# RS485_RGB_Power.net
KiCad netlist of a schematic drawn in Altium Designer
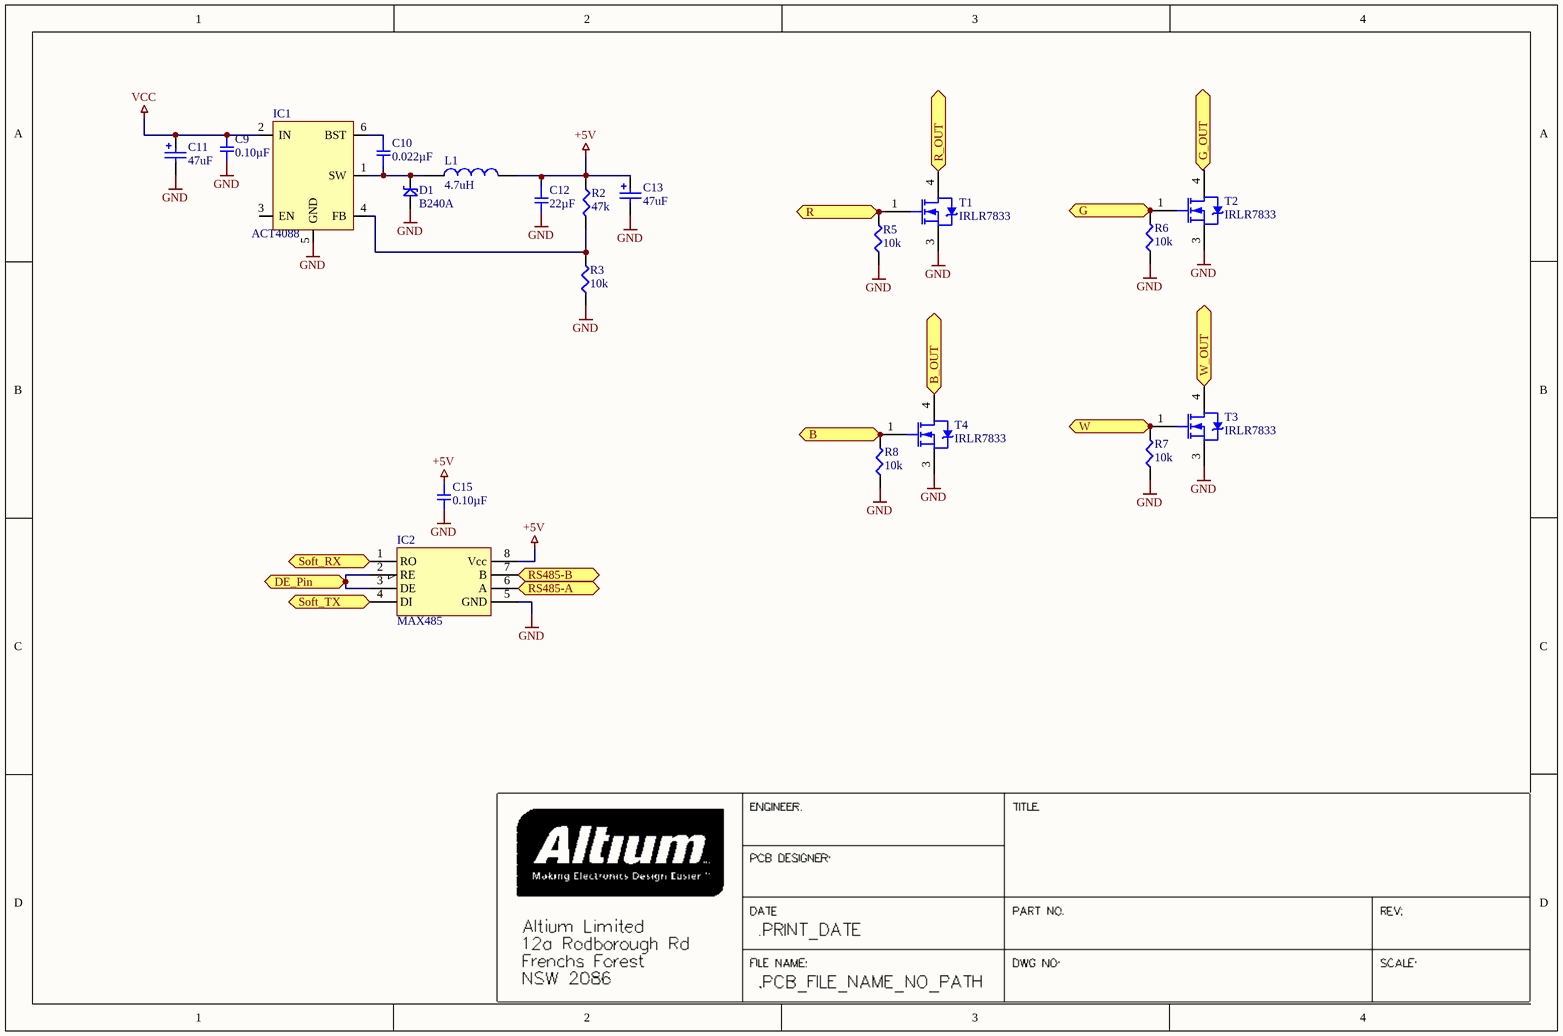
[diagram p0: RS485_RGB_Power.SchDoc]

(export (version "E")
  (design (tool "Eeschema 10.0.6"))
  (components
    (comp (ref "C9")
      (value "0.10µF")
      (footprint "SMD-0603C")
      (description "CAP CER 0.1UF 100V X7R 0603")
      (fields
        (field (name "DIGI-KEY PART NUMBER") "490-13420-1-ND")
        (field (name "PART NUMBER") "GCJ188R72A104KA01D")
      )
      (libsource (lib "capacitor_murata_0603") (part "GCJ188R72A104KA01D"))
    )
    (comp (ref "C10")
      (value "0.022µF")
      (footprint "SMD-0603C")
      (description "CAP CER 0.022UF 50V X7R 0603")
      (fields
        (field (name "DIGI-KEY PART NUMBER") "490-5851-1-ND")
        (field (name "PART NUMBER") "GCJ188R71H223KA01D")
      )
      (libsource (lib "capacitor_murata_0603") (part "GCJ188R71H223KA01D"))
    )
    (comp (ref "C11")
      (value "47uF")
      (footprint "WCAP-ASLI_6.3x5.5")
      (description "WCAP-ASLI Aluminum Electrolytic Capacitors, size Ф6.3x5.5mm, 35V DC, 47uF")
      (fields (field (name "PART NUMBER") "865080543009") (field (name "PUBLISHER") "Wurth Elektronik"))
      (libsource (lib "ALTIUM-WCAP-ASLI-rev17a") (part "865080543009"))
    )
    (comp (ref "C12")
      (value "22µF")
      (footprint "SMD-0603C")
      (description "CAP CER 22UF 4V X5R 0603")
      (fields
        (field (name "DIGI-KEY PART NUMBER") "490-13240-1-ND")
        (field (name "PART NUMBER") "GRM186R60G226ME15D")
      )
      (libsource (lib "capacitor_murata_0603") (part "GRM186R60G226ME15D"))
    )
    (comp (ref "C13")
      (value "47uF")
      (footprint "WCAP-ASLI_6.3x5.5")
      (description "WCAP-ASLI Aluminum Electrolytic Capacitors, size Ф6.3x5.5mm, 35V DC, 47uF")
      (fields (field (name "PART NUMBER") "865080543009") (field (name "PUBLISHER") "Wurth Elektronik"))
      (libsource (lib "ALTIUM-WCAP-ASLI-rev17a") (part "865080543009"))
    )
    (comp (ref "C15")
      (value "0.10µF")
      (footprint "SMD-0603C")
      (description "CAP CER 0.1UF 100V X7R 0603")
      (fields
        (field (name "DIGI-KEY PART NUMBER") "490-13420-1-ND")
        (field (name "PART NUMBER") "GCJ188R72A104KA01D")
      )
      (libsource (lib "capacitor_murata_0603") (part "GCJ188R72A104KA01D"))
    )
    (comp (ref "D1")
      (value "B240A")
      (footprint "B240A")
      (description "Shottkydiode")
      (libsource (lib "MyLibs") (part "B240A"))
    )
    (comp (ref "IC1") (value "ACT4088") (footprint "SOT23-6") (libsource (lib "MyLibs") (part "ACT4088")))
    (comp (ref "IC2") (value "MAX485") (footprint "D008_L") (libsource (lib "MyLibs") (part "MAX485")))
    (comp (ref "L1")
      (value "4.7uH")
      (footprint "WE-TPC_2813")
      (description "WE-TPC SMD Shielded Tiny Power Inductor, size 2813, 1A, 170mΩ, 4.7uH")
      (fields (field (name "PART NUMBER") "744029004") (field (name "PUBLISHER") "Wurth Elektronik"))
      (libsource (lib "ALTIUM-WE-TPC-rev17a") (part "744029004"))
    )
    (comp (ref "R2")
      (value "47k")
      (footprint "SMD-0603-RES")
      (description "RES SMD 47K OHM 1% 1/10W 0603")
      (fields
        (field (name "PART NUMBER") "ERJ-3EKF4702V")
        (field (name "DIGI-KEY PART NUMBER") "P47.0KHCT-ND")
      )
      (libsource (lib "Panasonic_ERJ_0603") (part "ERJ-3EKF4702V"))
    )
    (comp (ref "R3")
      (value "10k")
      (footprint "SMD-0603-RES")
      (description "RES SMD 10K OHM 1% 1/10W 0603")
      (fields
        (field (name "PART NUMBER") "ERJ-3EKF1002V")
        (field (name "DIGI-KEY PART NUMBER") "P10.0KHCT-ND")
      )
      (libsource (lib "Panasonic_ERJ_0603") (part "ERJ-3EKF1002V"))
    )
    (comp (ref "R5")
      (value "10k")
      (footprint "SMD-0603-RES")
      (description "RES SMD 10K OHM 1% 1/10W 0603")
      (fields
        (field (name "PART NUMBER") "ERJ-3EKF1002V")
        (field (name "DIGI-KEY PART NUMBER") "P10.0KHCT-ND")
      )
      (libsource (lib "Panasonic_ERJ_0603") (part "ERJ-3EKF1002V"))
    )
    (comp (ref "R6")
      (value "10k")
      (footprint "SMD-0603-RES")
      (description "RES SMD 10K OHM 1% 1/10W 0603")
      (fields
        (field (name "PART NUMBER") "ERJ-3EKF1002V")
        (field (name "DIGI-KEY PART NUMBER") "P10.0KHCT-ND")
      )
      (libsource (lib "Panasonic_ERJ_0603") (part "ERJ-3EKF1002V"))
    )
    (comp (ref "R7")
      (value "10k")
      (footprint "SMD-0603-RES")
      (description "RES SMD 10K OHM 1% 1/10W 0603")
      (fields
        (field (name "PART NUMBER") "ERJ-3EKF1002V")
        (field (name "DIGI-KEY PART NUMBER") "P10.0KHCT-ND")
      )
      (libsource (lib "Panasonic_ERJ_0603") (part "ERJ-3EKF1002V"))
    )
    (comp (ref "R8")
      (value "10k")
      (footprint "SMD-0603-RES")
      (description "RES SMD 10K OHM 1% 1/10W 0603")
      (fields
        (field (name "PART NUMBER") "ERJ-3EKF1002V")
        (field (name "DIGI-KEY PART NUMBER") "P10.0KHCT-ND")
      )
      (libsource (lib "Panasonic_ERJ_0603") (part "ERJ-3EKF1002V"))
    )
    (comp (ref "T1")
      (value "IRLR7833")
      (footprint "ONSC-DPAK-3-369C-01_V")
      (description "N-Channel MOSFET")
      (libsource (lib "MyLibs") (part "IRLR7833"))
    )
    (comp (ref "T2")
      (value "IRLR7833")
      (footprint "ONSC-DPAK-3-369C-01_V")
      (description "N-Channel MOSFET")
      (libsource (lib "MyLibs") (part "IRLR7833"))
    )
    (comp (ref "T3")
      (value "IRLR7833")
      (footprint "ONSC-DPAK-3-369C-01_V")
      (description "N-Channel MOSFET")
      (libsource (lib "MyLibs") (part "IRLR7833"))
    )
    (comp (ref "T4")
      (value "IRLR7833")
      (footprint "ONSC-DPAK-3-369C-01_V")
      (description "N-Channel MOSFET")
      (libsource (lib "MyLibs") (part "IRLR7833"))
    )
  )
  (nets
    (net (code "1") (name "+5V") (class "Default")
      (node (ref "C12") (pin "1") (pinfunction "1_1") (pintype "passive"))
      (node (ref "C13") (pin "1") (pinfunction "P_1") (pintype "passive"))
      (node (ref "C15") (pin "1") (pinfunction "1_1") (pintype "passive"))
      (node (ref "IC2") (pin "8") (pinfunction "Vcc_8") (pintype "passive"))
      (node (ref "L1") (pin "2") (pinfunction "2_2") (pintype "passive"))
      (node (ref "R2") (pin "1") (pinfunction "1_1") (pintype "passive"))
    )
    (net (code "2") (name "/B") (class "Default")
      (node (ref "R8") (pin "2") (pinfunction "2_2") (pintype "passive"))
      (node (ref "T4") (pin "1") (pinfunction "G_1") (pintype "passive"))
    )
    (net (code "3") (name "/B_OUT") (class "Default")
      (node (ref "T4") (pin "4") (pinfunction "D_4") (pintype "passive"))
    )
    (net (code "4") (name "/DE_Pin") (class "Default")
      (node (ref "IC2") (pin "2") (pinfunction "RE_2") (pintype "passive"))
      (node (ref "IC2") (pin "3") (pinfunction "DE_3") (pintype "passive"))
    )
    (net (code "5") (name "/G") (class "Default")
      (node (ref "R6") (pin "2") (pinfunction "2_2") (pintype "passive"))
      (node (ref "T2") (pin "1") (pinfunction "G_1") (pintype "passive"))
    )
    (net (code "6") (name "/G_OUT") (class "Default")
      (node (ref "T2") (pin "4") (pinfunction "D_4") (pintype "passive"))
    )
    (net (code "7") (name "/R") (class "Default")
      (node (ref "R5") (pin "2") (pinfunction "2_2") (pintype "passive"))
      (node (ref "T1") (pin "1") (pinfunction "G_1") (pintype "passive"))
    )
    (net (code "8") (name "/RS485-A") (class "Default")
      (node (ref "IC2") (pin "6") (pinfunction "A_6") (pintype "passive"))
    )
    (net (code "9") (name "/RS485-B") (class "Default")
      (node (ref "IC2") (pin "7") (pinfunction "B_7") (pintype "passive"))
    )
    (net (code "10") (name "/R_OUT") (class "Default")
      (node (ref "T1") (pin "4") (pinfunction "D_4") (pintype "passive"))
    )
    (net (code "11") (name "/Soft_RX") (class "Default")
      (node (ref "IC2") (pin "1") (pinfunction "RO_1") (pintype "passive"))
    )
    (net (code "12") (name "/Soft_TX") (class "Default")
      (node (ref "IC2") (pin "4") (pinfunction "DI_4") (pintype "passive"))
    )
    (net (code "13") (name "/W") (class "Default")
      (node (ref "R7") (pin "2") (pinfunction "2_2") (pintype "passive"))
      (node (ref "T3") (pin "1") (pinfunction "G_1") (pintype "passive"))
    )
    (net (code "14") (name "/W_OUT") (class "Default")
      (node (ref "T3") (pin "4") (pinfunction "D_4") (pintype "passive"))
    )
    (net (code "15") (name "GND") (class "Default")
      (node (ref "C11") (pin "2") (pinfunction "N_2") (pintype "passive"))
      (node (ref "C12") (pin "2") (pinfunction "2_2") (pintype "passive"))
      (node (ref "C13") (pin "2") (pinfunction "N_2") (pintype "passive"))
      (node (ref "C15") (pin "2") (pinfunction "2_2") (pintype "passive"))
      (node (ref "C9") (pin "2") (pinfunction "2_2") (pintype "passive"))
      (node (ref "D1") (pin "A") (pinfunction "A_A") (pintype "passive"))
      (node (ref "IC1") (pin "5") (pinfunction "GND_5") (pintype "passive"))
      (node (ref "IC2") (pin "5") (pinfunction "GND_5") (pintype "passive"))
      (node (ref "R3") (pin "1") (pinfunction "1_1") (pintype "passive"))
      (node (ref "R5") (pin "1") (pinfunction "1_1") (pintype "passive"))
      (node (ref "R6") (pin "1") (pinfunction "1_1") (pintype "passive"))
      (node (ref "R7") (pin "1") (pinfunction "1_1") (pintype "passive"))
      (node (ref "R8") (pin "1") (pinfunction "1_1") (pintype "passive"))
      (node (ref "T1") (pin "3") (pinfunction "S_3") (pintype "passive"))
      (node (ref "T2") (pin "3") (pinfunction "S_3") (pintype "passive"))
      (node (ref "T3") (pin "3") (pinfunction "S_3") (pintype "passive"))
      (node (ref "T4") (pin "3") (pinfunction "S_3") (pintype "passive"))
    )
    (net (code "16") (name "Net-(IC1-BST)") (class "Default")
      (node (ref "C10") (pin "1") (pinfunction "1_1") (pintype "passive"))
      (node (ref "IC1") (pin "6") (pinfunction "BST_6") (pintype "passive"))
    )
    (net (code "17") (name "Net-(IC1-FB)") (class "Default")
      (node (ref "IC1") (pin "4") (pinfunction "FB_4") (pintype "passive"))
      (node (ref "R2") (pin "2") (pinfunction "2_2") (pintype "passive"))
      (node (ref "R3") (pin "2") (pinfunction "2_2") (pintype "passive"))
    )
    (net (code "18") (name "Net-(IC1-SW)") (class "Default")
      (node (ref "C10") (pin "2") (pinfunction "2_2") (pintype "passive"))
      (node (ref "D1") (pin "K") (pinfunction "K_K") (pintype "passive"))
      (node (ref "IC1") (pin "1") (pinfunction "SW_1") (pintype "passive"))
      (node (ref "L1") (pin "1") (pinfunction "1_1") (pintype "passive"))
    )
    (net (code "19") (name "VCC") (class "Default")
      (node (ref "C11") (pin "1") (pinfunction "P_1") (pintype "passive"))
      (node (ref "C9") (pin "1") (pinfunction "1_1") (pintype "passive"))
      (node (ref "IC1") (pin "2") (pinfunction "IN_2") (pintype "passive"))
    )
    (net (code "20") (name "unconnected-(IC1-EN-Pad3)") (class "Default")
      (node (ref "IC1") (pin "3") (pinfunction "EN_3") (pintype "passive"))
    )
  )
)
